# L6983_Regulator_Board.net
KiCad netlist of a schematic drawn in EAGLE
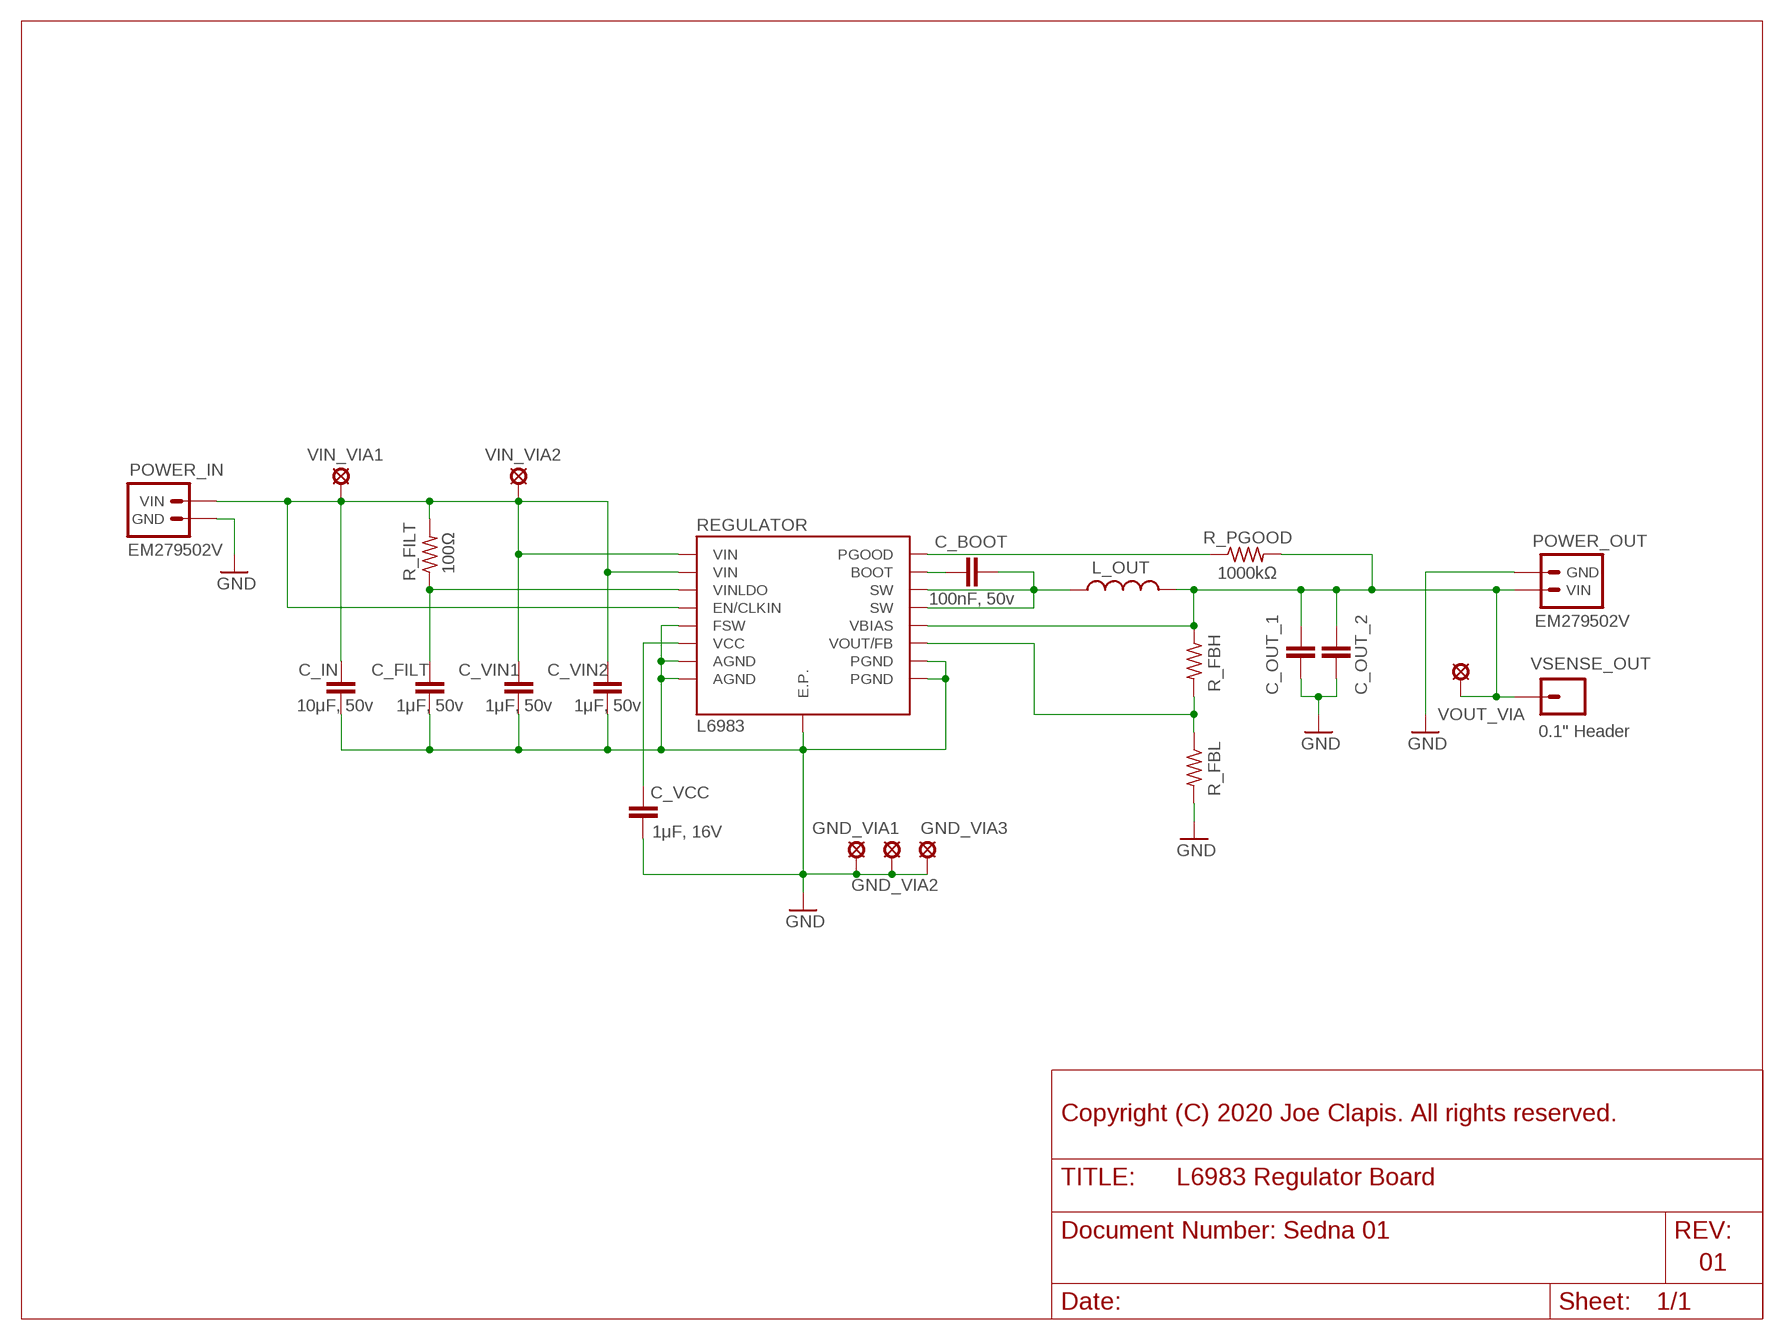
[diagram p0: schematic, sheet 1]

(export (version "E")
  (design (tool "Eeschema 10.0.6"))
  (components
    (comp (ref "C_BOOT")
      (value "100nF, 50v")
      (footprint "eagle-import:C0805")
      (libsource (lib "eagle-import") (part "C-EUC0805"))
    )
    (comp (ref "C_FILT")
      (value "1μF, 50v")
      (footprint "eagle-import:C0805")
      (libsource (lib "eagle-import") (part "C-EUC0805"))
    )
    (comp (ref "C_IN")
      (value "10μF, 50v")
      (footprint "eagle-import:C1206")
      (libsource (lib "eagle-import") (part "C-EUC1206"))
    )
    (comp (ref "C_OUT_1")
      (value "TDK_C2220_5750")
      (footprint "eagle-import:TDK_C2220_5750")
      (libsource (lib "eagle-import") (part "TDK_C2220_5750"))
    )
    (comp (ref "C_OUT_2")
      (value "TDK_C2220_5750")
      (footprint "eagle-import:TDK_C2220_5750")
      (libsource (lib "eagle-import") (part "TDK_C2220_5750"))
    )
    (comp (ref "C_VCC")
      (value "1μF, 16V")
      (footprint "eagle-import:C0805")
      (libsource (lib "eagle-import") (part "C-EUC0805"))
    )
    (comp (ref "C_VIN1")
      (value "1μF, 50v")
      (footprint "eagle-import:C0805")
      (libsource (lib "eagle-import") (part "C-EUC0805"))
    )
    (comp (ref "C_VIN2")
      (value "1μF, 50v")
      (footprint "eagle-import:C0805")
      (libsource (lib "eagle-import") (part "C-EUC0805"))
    )
    (comp (ref "GND_VIA1")
      (value "LSP13")
      (footprint "eagle-import:LSP13")
      (libsource (lib "eagle-import") (part "LSP13"))
    )
    (comp (ref "GND_VIA2")
      (value "LSP13")
      (footprint "eagle-import:LSP13")
      (libsource (lib "eagle-import") (part "LSP13"))
    )
    (comp (ref "GND_VIA3")
      (value "LSP13")
      (footprint "eagle-import:LSP13")
      (libsource (lib "eagle-import") (part "LSP13"))
    )
    (comp (ref "L_OUT")
      (value "PA4343_FP2")
      (footprint "eagle-import:PA4343_FP2")
      (libsource (lib "eagle-import") (part "PA4343_FP2"))
    )
    (comp (ref "POWER_IN")
      (value "EM279502V")
      (footprint "eagle-import:EM279502V")
      (libsource (lib "eagle-import") (part "EM279502V"))
    )
    (comp (ref "POWER_OUT")
      (value "EM279502V")
      (footprint "eagle-import:EM279502V")
      (libsource (lib "eagle-import") (part "EM279502V"))
    )
    (comp (ref "REGULATOR")
      (value "L6983")
      (footprint "eagle-import:L6983")
      (libsource (lib "eagle-import") (part "L6983"))
    )
    (comp (ref "R_FBH")
      (value "R-US_R0805")
      (footprint "eagle-import:R0805")
      (libsource (lib "eagle-import") (part "R-US_R0805"))
    )
    (comp (ref "R_FBL")
      (value "R-US_R0805")
      (footprint "eagle-import:R0805")
      (libsource (lib "eagle-import") (part "R-US_R0805"))
    )
    (comp (ref "R_FILT")
      (value "100Ω")
      (footprint "eagle-import:R0805")
      (libsource (lib "eagle-import") (part "R-US_R0805"))
    )
    (comp (ref "R_PGOOD")
      (value "1000kΩ")
      (footprint "eagle-import:R0805")
      (libsource (lib "eagle-import") (part "R-US_R0805"))
    )
    (comp (ref "VIN_VIA1")
      (value "LSP13")
      (footprint "eagle-import:LSP13")
      (libsource (lib "eagle-import") (part "LSP13"))
    )
    (comp (ref "VIN_VIA2")
      (value "LSP13")
      (footprint "eagle-import:LSP13")
      (libsource (lib "eagle-import") (part "LSP13"))
    )
    (comp (ref "VOUT_VIA")
      (value "LSP13")
      (footprint "eagle-import:LSP13")
      (libsource (lib "eagle-import") (part "LSP13"))
    )
    (comp (ref "VSENSE_OUT")
      (value "0.1\" Header")
      (footprint "eagle-import:1X01")
      (libsource (lib "eagle-import") (part "M01PTH"))
    )
  )
  (nets
    (net (code "1") (name "GND") (class "Default")
      (node (ref "C_FILT") (pin "2") (pinfunction "2_2") (pintype "passive"))
      (node (ref "C_IN") (pin "2") (pinfunction "2_2") (pintype "passive"))
      (node (ref "C_OUT_1") (pin "2") (pinfunction "2_2") (pintype "passive"))
      (node (ref "C_OUT_2") (pin "2") (pinfunction "2_2") (pintype "passive"))
      (node (ref "C_VCC") (pin "2") (pinfunction "2_2") (pintype "passive"))
      (node (ref "C_VIN1") (pin "2") (pinfunction "2_2") (pintype "passive"))
      (node (ref "C_VIN2") (pin "2") (pinfunction "2_2") (pintype "passive"))
      (node (ref "GND_VIA1") (pin "MP") (pinfunction "MP_MP") (pintype "passive"))
      (node (ref "GND_VIA2") (pin "MP") (pinfunction "MP_MP") (pintype "passive"))
      (node (ref "GND_VIA3") (pin "MP") (pinfunction "MP_MP") (pintype "passive"))
      (node (ref "POWER_IN") (pin "2A") (pinfunction "GND_2A") (pintype "passive"))
      (node (ref "POWER_IN") (pin "2B") (pinfunction "GND_2B") (pintype "passive"))
      (node (ref "POWER_OUT") (pin "2A") (pinfunction "GND_2A") (pintype "passive"))
      (node (ref "POWER_OUT") (pin "2B") (pinfunction "GND_2B") (pintype "passive"))
      (node (ref "REGULATOR") (pin "10_AGND") (pinfunction "AGND_10_AGND") (pintype "power_in"))
      (node (ref "REGULATOR") (pin "13_PGND") (pinfunction "PGND_13_PGND") (pintype "power_in"))
      (node (ref "REGULATOR") (pin "16_PGND") (pinfunction "PGND_16_PGND") (pintype "power_in"))
      (node (ref "REGULATOR") (pin "3_AGND") (pinfunction "AGND_3_AGND") (pintype "power_in"))
      (node (ref "REGULATOR") (pin "8_FSW") (pinfunction "FSW_8_FSW") (pintype "output"))
      (node (ref "REGULATOR") (pin "E.P.") (pinfunction "E.P._E.P.") (pintype "power_in"))
      (node (ref "R_FBL") (pin "2") (pinfunction "2_2") (pintype "passive"))
    )
    (net (code "2") (name "Net-(C_BOOT-Pad2)") (class "Default")
      (node (ref "C_BOOT") (pin "2") (pinfunction "2_2") (pintype "passive"))
      (node (ref "L_OUT") (pin "1") (pinfunction "1_1") (pintype "passive"))
      (node (ref "REGULATOR") (pin "14_SW") (pinfunction "SW_14_SW") (pintype "power_in"))
      (node (ref "REGULATOR") (pin "15_SW") (pinfunction "SW_15_SW") (pintype "power_in"))
    )
    (net (code "3") (name "Net-(REGULATOR-BOOT)") (class "Default")
      (node (ref "C_BOOT") (pin "1") (pinfunction "1_1") (pintype "passive"))
      (node (ref "REGULATOR") (pin "11_BOOT") (pinfunction "BOOT_11_BOOT") (pintype "power_in"))
    )
    (net (code "4") (name "Net-(REGULATOR-EN{slash}CLKIN)") (class "Default")
      (node (ref "C_IN") (pin "1") (pinfunction "1_1") (pintype "passive"))
      (node (ref "C_VIN1") (pin "1") (pinfunction "1_1") (pintype "passive"))
      (node (ref "C_VIN2") (pin "1") (pinfunction "1_1") (pintype "passive"))
      (node (ref "POWER_IN") (pin "1A") (pinfunction "VIN_1A") (pintype "passive"))
      (node (ref "POWER_IN") (pin "1B") (pinfunction "VIN_1B") (pintype "passive"))
      (node (ref "REGULATOR") (pin "12_VIN") (pinfunction "VIN_12_VIN") (pintype "power_in"))
      (node (ref "REGULATOR") (pin "1_VIN") (pinfunction "VIN_1_VIN") (pintype "power_in"))
      (node (ref "REGULATOR") (pin "4_EN/CLKIN") (pinfunction "EN/CLKIN_4_EN/CLKIN") (pintype "input"))
      (node (ref "R_FILT") (pin "2") (pinfunction "2_2") (pintype "passive"))
      (node (ref "VIN_VIA1") (pin "MP") (pinfunction "MP_MP") (pintype "passive"))
      (node (ref "VIN_VIA2") (pin "MP") (pinfunction "MP_MP") (pintype "passive"))
    )
    (net (code "5") (name "Net-(REGULATOR-PGOOD)") (class "Default")
      (node (ref "REGULATOR") (pin "5_PGOOD") (pinfunction "PGOOD_5_PGOOD") (pintype "output"))
      (node (ref "R_PGOOD") (pin "1") (pinfunction "1_1") (pintype "passive"))
    )
    (net (code "6") (name "Net-(REGULATOR-VBIAS)") (class "Default")
      (node (ref "C_OUT_1") (pin "1") (pinfunction "1_1") (pintype "passive"))
      (node (ref "C_OUT_2") (pin "1") (pinfunction "1_1") (pintype "passive"))
      (node (ref "L_OUT") (pin "2") (pinfunction "2_2") (pintype "passive"))
      (node (ref "POWER_OUT") (pin "1A") (pinfunction "VIN_1A") (pintype "passive"))
      (node (ref "POWER_OUT") (pin "1B") (pinfunction "VIN_1B") (pintype "passive"))
      (node (ref "REGULATOR") (pin "6_VBIAS") (pinfunction "VBIAS_6_VBIAS") (pintype "input"))
      (node (ref "R_FBH") (pin "1") (pinfunction "1_1") (pintype "passive"))
      (node (ref "R_PGOOD") (pin "2") (pinfunction "2_2") (pintype "passive"))
      (node (ref "VOUT_VIA") (pin "MP") (pinfunction "MP_MP") (pintype "passive"))
      (node (ref "VSENSE_OUT") (pin "1") (pinfunction "1_1") (pintype "passive"))
    )
    (net (code "7") (name "Net-(REGULATOR-VCC)") (class "Default")
      (node (ref "C_VCC") (pin "1") (pinfunction "1_1") (pintype "passive"))
      (node (ref "REGULATOR") (pin "9_VCC") (pinfunction "VCC_9_VCC") (pintype "power_in"))
    )
    (net (code "8") (name "Net-(REGULATOR-VINLDO)") (class "Default")
      (node (ref "C_FILT") (pin "1") (pinfunction "1_1") (pintype "passive"))
      (node (ref "REGULATOR") (pin "2_VINLDO") (pinfunction "VINLDO_2_VINLDO") (pintype "power_in"))
      (node (ref "R_FILT") (pin "1") (pinfunction "1_1") (pintype "passive"))
    )
    (net (code "9") (name "Net-(REGULATOR-VOUT{slash}FB)") (class "Default")
      (node (ref "REGULATOR") (pin "7_FB/VOUT") (pinfunction "VOUT/FB_7_FB/VOUT") (pintype "input"))
      (node (ref "R_FBH") (pin "2") (pinfunction "2_2") (pintype "passive"))
      (node (ref "R_FBL") (pin "1") (pinfunction "1_1") (pintype "passive"))
    )
  )
)
